# RAM.net
KiCad netlist of a schematic drawn in Altium Designer
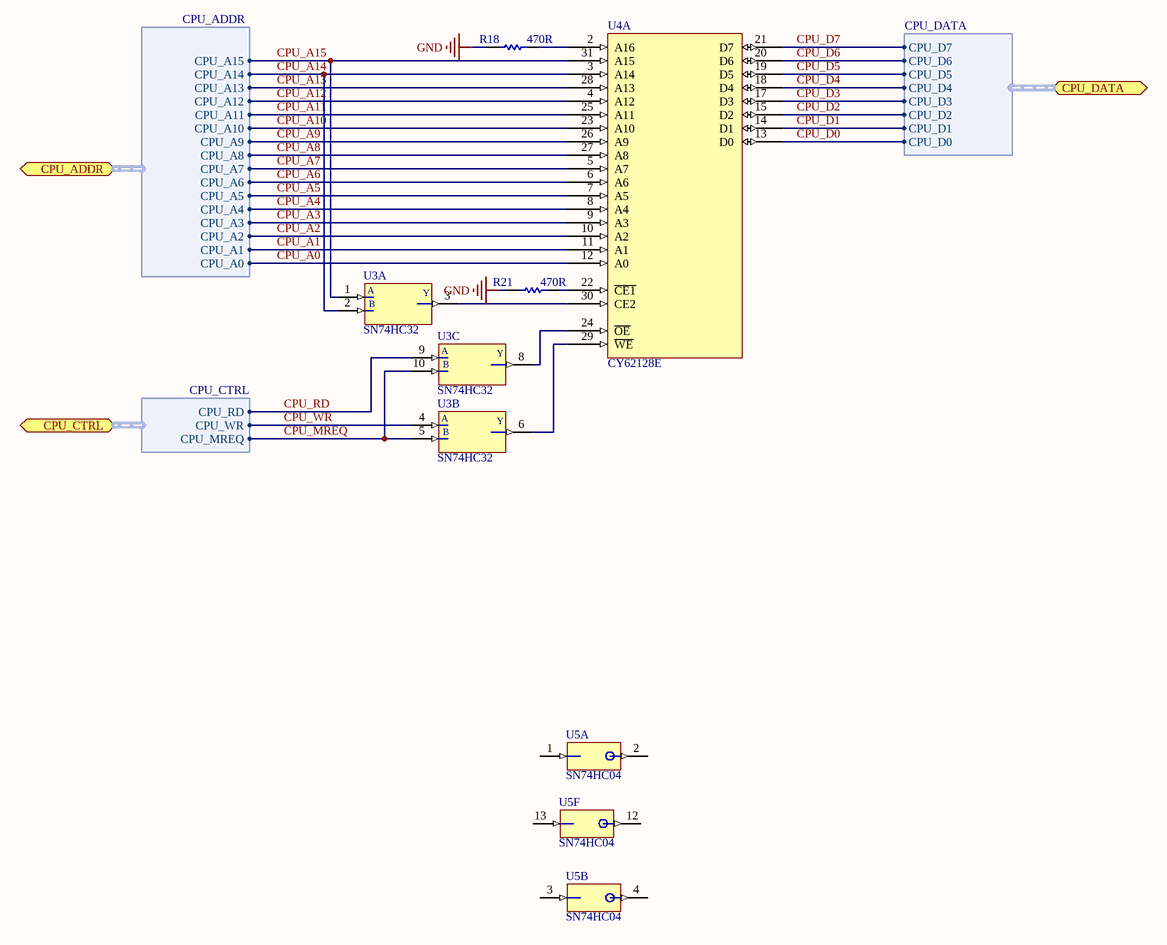
[diagram p0: RAM.SchDoc]

(export (version "E")
  (design (tool "Eeschema 10.0.6"))
  (components
    (comp (ref "R18")
      (value "470R")
      (footprint "0805")
      (description "Resistor")
      (libsource (lib "Basic") (part "Resistor"))
    )
    (comp (ref "R21")
      (value "470R")
      (footprint "0805")
      (description "Resistor")
      (libsource (lib "Basic") (part "Resistor"))
    )
    (comp (ref "U3")
      (value "SN74HC32")
      (footprint "SOIC14")
      (description "Quadruple 2-Input Positive-OR Gates")
      (libsource (lib "Texas Instruments") (part "SN74HC32"))
    )
    (comp (ref "U4")
      (value "CY62128E")
      (footprint "CY62128E-SOIC")
      (description "128KB Static RAM")
      (libsource (lib "Infineon") (part "CY62128E"))
    )
    (comp (ref "U5")
      (value "SN74HC04")
      (footprint "SOIC14")
      (description "Hex Inverters")
      (libsource (lib "Texas Instruments") (part "SN74HC04"))
    )
  )
  (nets
    (net (code "4") (name "/CPU_A0") (class "Default")
      (node (ref "U4") (pin "12") (pinfunction "A0_12") (pintype "input"))
    )
    (net (code "5") (name "/CPU_A1") (class "Default")
      (node (ref "U4") (pin "11") (pinfunction "A1_11") (pintype "input"))
    )
    (net (code "6") (name "/CPU_A2") (class "Default")
      (node (ref "U4") (pin "10") (pinfunction "A2_10") (pintype "input"))
    )
    (net (code "7") (name "/CPU_A3") (class "Default")
      (node (ref "U4") (pin "9") (pinfunction "A3_9") (pintype "input"))
    )
    (net (code "8") (name "/CPU_A4") (class "Default")
      (node (ref "U4") (pin "8") (pinfunction "A4_8") (pintype "input"))
    )
    (net (code "9") (name "/CPU_A5") (class "Default")
      (node (ref "U4") (pin "7") (pinfunction "A5_7") (pintype "input"))
    )
    (net (code "10") (name "/CPU_A6") (class "Default")
      (node (ref "U4") (pin "6") (pinfunction "A6_6") (pintype "input"))
    )
    (net (code "11") (name "/CPU_A7") (class "Default")
      (node (ref "U4") (pin "5") (pinfunction "A7_5") (pintype "input"))
    )
    (net (code "12") (name "/CPU_A8") (class "Default")
      (node (ref "U4") (pin "27") (pinfunction "A8_27") (pintype "input"))
    )
    (net (code "13") (name "/CPU_A9") (class "Default")
      (node (ref "U4") (pin "26") (pinfunction "A9_26") (pintype "input"))
    )
    (net (code "14") (name "/CPU_A10") (class "Default")
      (node (ref "U4") (pin "23") (pinfunction "A10_23") (pintype "input"))
    )
    (net (code "15") (name "/CPU_A11") (class "Default")
      (node (ref "U4") (pin "25") (pinfunction "A11_25") (pintype "input"))
    )
    (net (code "16") (name "/CPU_A12") (class "Default")
      (node (ref "U4") (pin "4") (pinfunction "A12_4") (pintype "input"))
    )
    (net (code "17") (name "/CPU_A13") (class "Default")
      (node (ref "U4") (pin "28") (pinfunction "A13_28") (pintype "input"))
    )
    (net (code "18") (name "/CPU_A14") (class "Default")
      (node (ref "U3") (pin "2") (pinfunction "B_2") (pintype "input"))
      (node (ref "U4") (pin "3") (pinfunction "A14_3") (pintype "input"))
    )
    (net (code "19") (name "/CPU_A15") (class "Default")
      (node (ref "U3") (pin "1") (pinfunction "A_1") (pintype "input"))
      (node (ref "U4") (pin "31") (pinfunction "A15_31") (pintype "input"))
    )
    (net (code "20") (name "/CPU_D0") (class "Default")
      (node (ref "U4") (pin "13") (pinfunction "D0_13") (pintype "bidirectional"))
    )
    (net (code "21") (name "/CPU_D1") (class "Default")
      (node (ref "U4") (pin "14") (pinfunction "D1_14") (pintype "bidirectional"))
    )
    (net (code "22") (name "/CPU_D2") (class "Default")
      (node (ref "U4") (pin "15") (pinfunction "D2_15") (pintype "bidirectional"))
    )
    (net (code "23") (name "/CPU_D3") (class "Default")
      (node (ref "U4") (pin "17") (pinfunction "D3_17") (pintype "bidirectional"))
    )
    (net (code "24") (name "/CPU_D4") (class "Default")
      (node (ref "U4") (pin "18") (pinfunction "D4_18") (pintype "bidirectional"))
    )
    (net (code "25") (name "/CPU_D5") (class "Default")
      (node (ref "U4") (pin "19") (pinfunction "D5_19") (pintype "bidirectional"))
    )
    (net (code "26") (name "/CPU_D6") (class "Default")
      (node (ref "U4") (pin "20") (pinfunction "D6_20") (pintype "bidirectional"))
    )
    (net (code "27") (name "/CPU_D7") (class "Default")
      (node (ref "U4") (pin "21") (pinfunction "D7_21") (pintype "bidirectional"))
    )
    (net (code "28") (name "/CPU_MREQ") (class "Default")
      (node (ref "U3") (pin "10") (pinfunction "B_10") (pintype "input"))
      (node (ref "U3") (pin "5") (pinfunction "B_5") (pintype "input"))
    )
    (net (code "29") (name "/CPU_RD") (class "Default")
      (node (ref "U3") (pin "9") (pinfunction "A_9") (pintype "input"))
    )
    (net (code "30") (name "/CPU_WR") (class "Default")
      (node (ref "U3") (pin "4") (pinfunction "A_4") (pintype "input"))
    )
    (net (code "34") (name "GND") (class "Default")
      (node (ref "R18") (pin "2") (pinfunction "2_2") (pintype "passive"))
      (node (ref "R21") (pin "2") (pinfunction "2_2") (pintype "passive"))
    )
    (net (code "35") (name "Net-(U3A-Y)") (class "Default")
      (node (ref "U3") (pin "3") (pinfunction "Y_3") (pintype "output"))
      (node (ref "U4") (pin "30") (pinfunction "CE2_30") (pintype "input"))
    )
    (net (code "36") (name "Net-(U3B-Y)") (class "Default")
      (node (ref "U3") (pin "6") (pinfunction "Y_6") (pintype "output"))
      (node (ref "U4") (pin "29") (pinfunction "~{WE}_29") (pintype "input"))
    )
    (net (code "37") (name "Net-(U3C-Y)") (class "Default")
      (node (ref "U3") (pin "8") (pinfunction "Y_8") (pintype "output"))
      (node (ref "U4") (pin "24") (pinfunction "~{OE}_24") (pintype "input"))
    )
    (net (code "38") (name "Net-(U4A-A16)") (class "Default")
      (node (ref "R18") (pin "1") (pinfunction "1_1") (pintype "passive"))
      (node (ref "U4") (pin "2") (pinfunction "A16_2") (pintype "input"))
    )
    (net (code "39") (name "Net-(U4A-~{CE1})") (class "Default")
      (node (ref "R21") (pin "1") (pinfunction "1_1") (pintype "passive"))
      (node (ref "U4") (pin "22") (pinfunction "~{CE1}_22") (pintype "input"))
    )
    (net (code "40") (name "unconnected-(U5A-A-Pad1)") (class "Default")
      (node (ref "U5") (pin "1") (pinfunction "A_1") (pintype "input"))
    )
    (net (code "41") (name "unconnected-(U5A-Y-Pad2)") (class "Default")
      (node (ref "U5") (pin "2") (pinfunction "Y_2") (pintype "output"))
    )
    (net (code "42") (name "unconnected-(U5B-A-Pad3)") (class "Default")
      (node (ref "U5") (pin "3") (pinfunction "A_3") (pintype "input"))
    )
    (net (code "43") (name "unconnected-(U5B-Y-Pad4)") (class "Default")
      (node (ref "U5") (pin "4") (pinfunction "Y_4") (pintype "output"))
    )
    (net (code "44") (name "unconnected-(U5F-A-Pad13)") (class "Default")
      (node (ref "U5") (pin "13") (pinfunction "A_13") (pintype "input"))
    )
    (net (code "45") (name "unconnected-(U5F-Y-Pad12)") (class "Default")
      (node (ref "U5") (pin "12") (pinfunction "Y_12") (pintype "output"))
    )
  )
)
